# IO_Hall_Sensor_SMD_Sch.net
KiCad netlist of a schematic drawn in Altium Designer
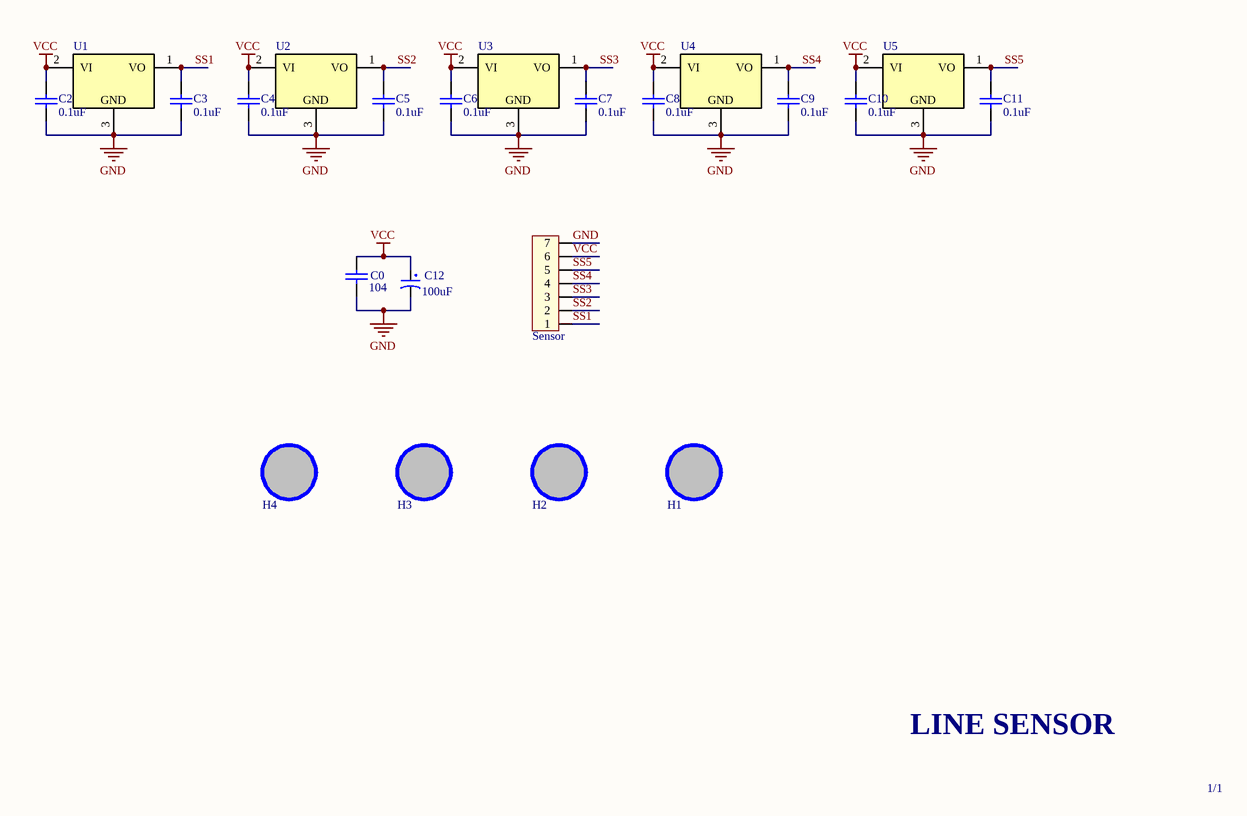
[diagram p0: IO_Hall_Sensor_SMD_Sch.SchDoc]

(export (version "E")
  (design (tool "Eeschema 10.0.6"))
  (components
    (comp (ref "C0")
      (value "104")
      (footprint "CAP-SM-0603")
      (description "Cắm")
      (libsource (lib "Altium_Lib_by_KhueNguyenCreator") (part "Tu gom 104 50V"))
    )
    (comp (ref "C2")
      (value "0.1uF")
      (footprint "CAP-SM-0603")
      (description "Dán")
      (libsource (lib "Altium_Lib_by_KhueNguyenCreator") (part "Tu 0805 476 6.3V 20%"))
    )
    (comp (ref "C3")
      (value "0.1uF")
      (footprint "CAP-SM-0603")
      (description "Dán")
      (libsource (lib "Altium_Lib_by_KhueNguyenCreator") (part "Tu 0805 476 6.3V 20%"))
    )
    (comp (ref "C4")
      (value "0.1uF")
      (footprint "CAP-SM-0603")
      (description "Dán")
      (libsource (lib "Altium_Lib_by_KhueNguyenCreator") (part "Tu 0805 476 6.3V 20%"))
    )
    (comp (ref "C5")
      (value "0.1uF")
      (footprint "CAP-SM-0603")
      (description "Dán")
      (libsource (lib "Altium_Lib_by_KhueNguyenCreator") (part "Tu 0805 476 6.3V 20%"))
    )
    (comp (ref "C6")
      (value "0.1uF")
      (footprint "CAP-SM-0603")
      (description "Dán")
      (libsource (lib "Altium_Lib_by_KhueNguyenCreator") (part "Tu 0805 476 6.3V 20%"))
    )
    (comp (ref "C7")
      (value "0.1uF")
      (footprint "CAP-SM-0603")
      (description "Dán")
      (libsource (lib "Altium_Lib_by_KhueNguyenCreator") (part "Tu 0805 476 6.3V 20%"))
    )
    (comp (ref "C8")
      (value "0.1uF")
      (footprint "CAP-SM-0603")
      (description "Dán")
      (libsource (lib "Altium_Lib_by_KhueNguyenCreator") (part "Tu 0805 476 6.3V 20%"))
    )
    (comp (ref "C9")
      (value "0.1uF")
      (footprint "CAP-SM-0603")
      (description "Dán")
      (libsource (lib "Altium_Lib_by_KhueNguyenCreator") (part "Tu 0805 476 6.3V 20%"))
    )
    (comp (ref "C10")
      (value "0.1uF")
      (footprint "CAP-SM-0603")
      (description "Dán")
      (libsource (lib "Altium_Lib_by_KhueNguyenCreator") (part "Tu 0805 476 6.3V 20%"))
    )
    (comp (ref "C11")
      (value "0.1uF")
      (footprint "CAP-SM-0603")
      (description "Dán")
      (libsource (lib "Altium_Lib_by_KhueNguyenCreator") (part "Tu 0805 476 6.3V 20%"))
    )
    (comp (ref "C12")
      (value "100uF")
      (footprint "tu tantalum smd3528")
      (description "Dán")
      (libsource (lib "Altium_Lib_by_KhueNguyenCreator") (part "Tu tantalum 100uF 50V SMD7343"))
    )
    (comp (ref "H1")
      (value "Hole")
      (footprint "LO KHOAN 3MM")
      (description "Hole 3mm")
      (libsource (lib "PIF_Library") (part "Hole"))
    )
    (comp (ref "H2")
      (value "Hole")
      (footprint "LO KHOAN 3MM")
      (description "Hole 3mm")
      (libsource (lib "PIF_Library") (part "Hole"))
    )
    (comp (ref "H3")
      (value "Hole")
      (footprint "LO KHOAN 3MM")
      (description "Hole 3mm")
      (libsource (lib "PIF_Library") (part "Hole"))
    )
    (comp (ref "H4")
      (value "Hole")
      (footprint "LO KHOAN 3MM")
      (description "Hole 3mm")
      (libsource (lib "PIF_Library") (part "Hole"))
    )
    (comp (ref "Sensor")
      (value "Sensor")
      (footprint "Header 7P DC 2.54")
      (description "Cắm")
      (libsource (lib "Altium_Lib_by_KhueNguyenCreator") (part "Header 7P 2.54 Duc Cong"))
    )
    (comp (ref "U1")
      (value "~")
      (footprint "SOT 23-3")
      (description "Linear Voltage Regulator IC 1 Output 100mA SOT-23-3")
      (fields
        (field (name "MANUFACTURER") "Texas Instruments")
        (field (name "MANUFACTURER PART NUMBER") "LM3480IM3-5.0/NOPB")
      )
      (libsource (lib "Altium_Lib_by_KhueNguyenCreator") (part "REG_30V-5V-100mA-1.4W-SOT23-3_2"))
    )
    (comp (ref "U2")
      (value "~")
      (footprint "SOT 23-3")
      (description "Linear Voltage Regulator IC 1 Output 100mA SOT-23-3")
      (fields
        (field (name "MANUFACTURER") "Texas Instruments")
        (field (name "MANUFACTURER PART NUMBER") "LM3480IM3-5.0/NOPB")
      )
      (libsource (lib "Altium_Lib_by_KhueNguyenCreator") (part "REG_30V-5V-100mA-1.4W-SOT23-3_2"))
    )
    (comp (ref "U3")
      (value "~")
      (footprint "SOT 23-3")
      (description "Linear Voltage Regulator IC 1 Output 100mA SOT-23-3")
      (fields
        (field (name "MANUFACTURER") "Texas Instruments")
        (field (name "MANUFACTURER PART NUMBER") "LM3480IM3-5.0/NOPB")
      )
      (libsource (lib "Altium_Lib_by_KhueNguyenCreator") (part "REG_30V-5V-100mA-1.4W-SOT23-3_2"))
    )
    (comp (ref "U4")
      (value "~")
      (footprint "SOT 23-3")
      (description "Linear Voltage Regulator IC 1 Output 100mA SOT-23-3")
      (fields
        (field (name "MANUFACTURER") "Texas Instruments")
        (field (name "MANUFACTURER PART NUMBER") "LM3480IM3-5.0/NOPB")
      )
      (libsource (lib "Altium_Lib_by_KhueNguyenCreator") (part "REG_30V-5V-100mA-1.4W-SOT23-3_2"))
    )
    (comp (ref "U5")
      (value "~")
      (footprint "SOT 23-3")
      (description "Linear Voltage Regulator IC 1 Output 100mA SOT-23-3")
      (fields
        (field (name "MANUFACTURER") "Texas Instruments")
        (field (name "MANUFACTURER PART NUMBER") "LM3480IM3-5.0/NOPB")
      )
      (libsource (lib "Altium_Lib_by_KhueNguyenCreator") (part "REG_30V-5V-100mA-1.4W-SOT23-3_2"))
    )
  )
  (nets
    (net (code "1") (name "/SS1") (class "Default")
      (node (ref "C3") (pin "1") (pinfunction "1_1") (pintype "passive"))
      (node (ref "Sensor") (pin "1") (pinfunction "1_1") (pintype "passive"))
      (node (ref "U1") (pin "1") (pinfunction "VO_1") (pintype "passive"))
    )
    (net (code "2") (name "/SS2") (class "Default")
      (node (ref "C5") (pin "1") (pinfunction "1_1") (pintype "passive"))
      (node (ref "Sensor") (pin "2") (pinfunction "2_2") (pintype "passive"))
      (node (ref "U2") (pin "1") (pinfunction "VO_1") (pintype "passive"))
    )
    (net (code "3") (name "/SS3") (class "Default")
      (node (ref "C7") (pin "1") (pinfunction "1_1") (pintype "passive"))
      (node (ref "Sensor") (pin "3") (pinfunction "3_3") (pintype "passive"))
      (node (ref "U3") (pin "1") (pinfunction "VO_1") (pintype "passive"))
    )
    (net (code "4") (name "/SS4") (class "Default")
      (node (ref "C9") (pin "1") (pinfunction "1_1") (pintype "passive"))
      (node (ref "Sensor") (pin "4") (pinfunction "4_4") (pintype "passive"))
      (node (ref "U4") (pin "1") (pinfunction "VO_1") (pintype "passive"))
    )
    (net (code "5") (name "/SS5") (class "Default")
      (node (ref "C11") (pin "1") (pinfunction "1_1") (pintype "passive"))
      (node (ref "Sensor") (pin "5") (pinfunction "5_5") (pintype "passive"))
      (node (ref "U5") (pin "1") (pinfunction "VO_1") (pintype "passive"))
    )
    (net (code "6") (name "GND") (class "Default")
      (node (ref "C0") (pin "1") (pinfunction "1_1") (pintype "passive"))
      (node (ref "C10") (pin "2") (pinfunction "2_2") (pintype "passive"))
      (node (ref "C11") (pin "2") (pinfunction "2_2") (pintype "passive"))
      (node (ref "C12") (pin "2") (pinfunction "2_2") (pintype "passive"))
      (node (ref "C2") (pin "2") (pinfunction "2_2") (pintype "passive"))
      (node (ref "C3") (pin "2") (pinfunction "2_2") (pintype "passive"))
      (node (ref "C4") (pin "2") (pinfunction "2_2") (pintype "passive"))
      (node (ref "C5") (pin "2") (pinfunction "2_2") (pintype "passive"))
      (node (ref "C6") (pin "2") (pinfunction "2_2") (pintype "passive"))
      (node (ref "C7") (pin "2") (pinfunction "2_2") (pintype "passive"))
      (node (ref "C8") (pin "2") (pinfunction "2_2") (pintype "passive"))
      (node (ref "C9") (pin "2") (pinfunction "2_2") (pintype "passive"))
      (node (ref "Sensor") (pin "7") (pinfunction "7_7") (pintype "passive"))
      (node (ref "U1") (pin "3") (pintype "passive"))
      (node (ref "U2") (pin "3") (pintype "passive"))
      (node (ref "U3") (pin "3") (pintype "passive"))
      (node (ref "U4") (pin "3") (pintype "passive"))
      (node (ref "U5") (pin "3") (pintype "passive"))
    )
    (net (code "7") (name "VCC") (class "Default")
      (node (ref "C0") (pin "2") (pinfunction "2_2") (pintype "passive"))
      (node (ref "C10") (pin "1") (pinfunction "1_1") (pintype "passive"))
      (node (ref "C12") (pin "1") (pinfunction "1_1") (pintype "passive"))
      (node (ref "C2") (pin "1") (pinfunction "1_1") (pintype "passive"))
      (node (ref "C4") (pin "1") (pinfunction "1_1") (pintype "passive"))
      (node (ref "C6") (pin "1") (pinfunction "1_1") (pintype "passive"))
      (node (ref "C8") (pin "1") (pinfunction "1_1") (pintype "passive"))
      (node (ref "Sensor") (pin "6") (pinfunction "6_6") (pintype "passive"))
      (node (ref "U1") (pin "2") (pinfunction "VI_2") (pintype "passive"))
      (node (ref "U2") (pin "2") (pinfunction "VI_2") (pintype "passive"))
      (node (ref "U3") (pin "2") (pinfunction "VI_2") (pintype "passive"))
      (node (ref "U4") (pin "2") (pinfunction "VI_2") (pintype "passive"))
      (node (ref "U5") (pin "2") (pinfunction "VI_2") (pintype "passive"))
    )
    (net (code "8") (name "unconnected-(H1-Pad1)") (class "Default")
      (node (ref "H1") (pin "1") (pinfunction "1_1") (pintype "passive"))
    )
    (net (code "9") (name "unconnected-(H2-Pad1)") (class "Default")
      (node (ref "H2") (pin "1") (pinfunction "1_1") (pintype "passive"))
    )
    (net (code "10") (name "unconnected-(H3-Pad1)") (class "Default")
      (node (ref "H3") (pin "1") (pinfunction "1_1") (pintype "passive"))
    )
    (net (code "11") (name "unconnected-(H4-Pad1)") (class "Default")
      (node (ref "H4") (pin "1") (pinfunction "1_1") (pintype "passive"))
    )
  )
)
